# TPS61377_16V.net
KiCad netlist of a schematic drawn in Altium Designer
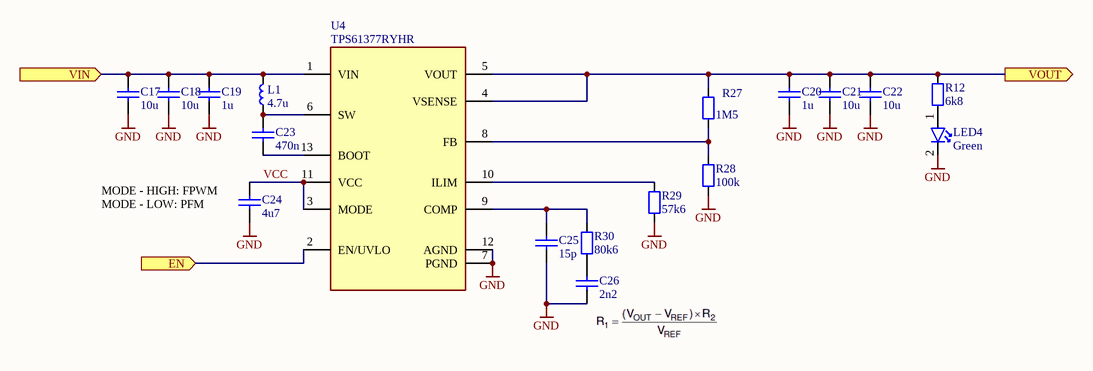
[diagram p0: TPS61377_16V.SchDoc]

(export (version "E")
  (design (tool "Eeschema 10.0.6"))
  (components
    (comp (ref "C17")
      (value "10u")
      (footprint "C_1206_3216Metric_IPC_N")
      (description "Generic MLCC with 1206 Footprint")
      (libsource (lib "database_library") (part "Capacitor_unpol"))
    )
    (comp (ref "C18")
      (value "10u")
      (footprint "C_1206_3216Metric_IPC_N")
      (description "Generic MLCC with 1206 Footprint")
      (libsource (lib "database_library") (part "Capacitor_unpol"))
    )
    (comp (ref "C19")
      (value "1u")
      (footprint "C_0402_1005Metric_IPC_N")
      (description "Generic MLCC with 0402 Footprint")
      (libsource (lib "database_library") (part "Capacitor_unpol"))
    )
    (comp (ref "C20")
      (value "1u")
      (footprint "C_0402_1005Metric_IPC_N")
      (description "Generic MLCC with 0402 Footprint")
      (libsource (lib "database_library") (part "Capacitor_unpol"))
    )
    (comp (ref "C21")
      (value "10u")
      (footprint "C_1206_3216Metric_IPC_N")
      (description "Generic MLCC with 1206 Footprint")
      (libsource (lib "database_library") (part "Capacitor_unpol"))
    )
    (comp (ref "C22")
      (value "10u")
      (footprint "C_1206_3216Metric_IPC_N")
      (description "Generic MLCC with 1206 Footprint")
      (libsource (lib "database_library") (part "Capacitor_unpol"))
    )
    (comp (ref "C23")
      (value "470n")
      (footprint "C_0402_1005Metric_IPC_N")
      (description "Generic MLCC with 0402 Footprint")
      (libsource (lib "database_library") (part "Capacitor_unpol"))
    )
    (comp (ref "C24")
      (value "4u7")
      (footprint "C_0402_1005Metric_IPC_N")
      (description "Generic MLCC with 0402 Footprint")
      (libsource (lib "database_library") (part "Capacitor_unpol"))
    )
    (comp (ref "C25")
      (value "15p")
      (footprint "C_0402_1005Metric_IPC_N")
      (description "Generic MLCC with 0402 Footprint")
      (libsource (lib "database_library") (part "Capacitor_unpol"))
    )
    (comp (ref "C26")
      (value "2n2")
      (footprint "C_0402_1005Metric_IPC_N")
      (description "Generic MLCC with 0402 Footprint")
      (libsource (lib "database_library") (part "Capacitor_unpol"))
    )
    (comp (ref "L1")
      (value "4.7u")
      (footprint "L_1616_4040Metric_IPC_N")
      (description "Power Inductor, 4.7u, 5A, , 57m, 20%, 1616")
      (fields (field (name "TOLERANCE") "20%") (field (name "MANUFACTURER") "Coilcraft"))
      (libsource (lib "database_library") (part "Inductor"))
    )
    (comp (ref "LED4")
      (value "Green")
      (footprint "LED_0603_1806Metric_IPC_N")
      (description "MLCC, Low Current, Green, 2.2V, 20mA, 0603")
      (fields
        (field (name "MANUFACTURER") "Broadcom / Avago")
        (field (name "MANUFACTURER PART NUMBER") "HSMG-C190")
      )
      (libsource (lib "database_library") (part "LED"))
    )
    (comp (ref "R12")
      (value "6k8")
      (footprint "R_0402_1005Metric_IPC_N")
      (description "Generic Chip Resistor with 0402 Footprint")
      (libsource (lib "database_library") (part "Resistor"))
    )
    (comp (ref "R27")
      (value "1M5")
      (footprint "R_0402_1005Metric_IPC_N")
      (description "Generic Chip Resistor with 0402 Footprint")
      (libsource (lib "database_library") (part "Resistor"))
    )
    (comp (ref "R28")
      (value "100k")
      (footprint "R_0402_1005Metric_IPC_N")
      (description "Generic Chip Resistor with 0402 Footprint")
      (libsource (lib "database_library") (part "Resistor"))
    )
    (comp (ref "R29")
      (value "57k6")
      (footprint "R_0402_1005Metric_IPC_N")
      (description "Generic Chip Resistor with 0402 Footprint")
      (libsource (lib "database_library") (part "Resistor"))
    )
    (comp (ref "R30")
      (value "80k6")
      (footprint "R_0402_1005Metric_IPC_N")
      (description "Generic Chip Resistor with 0402 Footprint")
      (libsource (lib "database_library") (part "Resistor"))
    )
    (comp (ref "U4")
      (value "TPS61377RYHR")
      (footprint "VQFN13_2_5x2")
      (fields (field (name "MANUFACTURER") "Texas Instruments"))
      (libsource (lib "database_library") (part "TPS61377RYHR"))
    )
  )
  (nets
    (net (code "1") (name "/EN") (class "Default")
      (node (ref "U4") (pin "2") (pinfunction "EN/UVLO_2") (pintype "passive"))
    )
    (net (code "2") (name "/VCC") (class "Default")
      (node (ref "C24") (pin "2") (pinfunction "2_2") (pintype "passive"))
      (node (ref "U4") (pin "11") (pinfunction "VCC_11") (pintype "passive"))
      (node (ref "U4") (pin "3") (pinfunction "MODE_3") (pintype "passive"))
    )
    (net (code "3") (name "/VIN") (class "Default")
      (node (ref "C17") (pin "2") (pinfunction "2_2") (pintype "passive"))
      (node (ref "C18") (pin "2") (pinfunction "2_2") (pintype "passive"))
      (node (ref "C19") (pin "2") (pinfunction "2_2") (pintype "passive"))
      (node (ref "L1") (pin "2") (pinfunction "2_2") (pintype "passive"))
      (node (ref "U4") (pin "1") (pinfunction "VIN_1") (pintype "passive"))
    )
    (net (code "4") (name "/VOUT") (class "Default")
      (node (ref "C20") (pin "2") (pinfunction "2_2") (pintype "passive"))
      (node (ref "C21") (pin "2") (pinfunction "2_2") (pintype "passive"))
      (node (ref "C22") (pin "2") (pinfunction "2_2") (pintype "passive"))
      (node (ref "R12") (pin "1") (pinfunction "1_1") (pintype "passive"))
      (node (ref "R27") (pin "2") (pinfunction "2_2") (pintype "passive"))
      (node (ref "U4") (pin "4") (pinfunction "VSENSE_4") (pintype "passive"))
      (node (ref "U4") (pin "5") (pinfunction "VOUT_5") (pintype "passive"))
    )
    (net (code "5") (name "GND") (class "Default")
      (node (ref "C17") (pin "1") (pinfunction "1_1") (pintype "passive"))
      (node (ref "C18") (pin "1") (pinfunction "1_1") (pintype "passive"))
      (node (ref "C19") (pin "1") (pinfunction "1_1") (pintype "passive"))
      (node (ref "C20") (pin "1") (pinfunction "1_1") (pintype "passive"))
      (node (ref "C21") (pin "1") (pinfunction "1_1") (pintype "passive"))
      (node (ref "C22") (pin "1") (pinfunction "1_1") (pintype "passive"))
      (node (ref "C24") (pin "1") (pinfunction "1_1") (pintype "passive"))
      (node (ref "C25") (pin "1") (pinfunction "1_1") (pintype "passive"))
      (node (ref "C26") (pin "1") (pinfunction "1_1") (pintype "passive"))
      (node (ref "LED4") (pin "2") (pinfunction "2_2") (pintype "passive"))
      (node (ref "R28") (pin "1") (pinfunction "1_1") (pintype "passive"))
      (node (ref "R29") (pin "1") (pinfunction "1_1") (pintype "passive"))
      (node (ref "U4") (pin "12") (pinfunction "AGND_12") (pintype "passive"))
      (node (ref "U4") (pin "7") (pinfunction "PGND_7") (pintype "passive"))
    )
    (net (code "6") (name "Net-(C26-Pad2)") (class "Default")
      (node (ref "C26") (pin "2") (pinfunction "2_2") (pintype "passive"))
      (node (ref "R30") (pin "1") (pinfunction "1_1") (pintype "passive"))
    )
    (net (code "7") (name "Net-(LED4-Pad1)") (class "Default")
      (node (ref "LED4") (pin "1") (pinfunction "1_1") (pintype "passive"))
      (node (ref "R12") (pin "2") (pinfunction "2_2") (pintype "passive"))
    )
    (net (code "8") (name "Net-(U4-BOOT)") (class "Default")
      (node (ref "C23") (pin "1") (pinfunction "1_1") (pintype "passive"))
      (node (ref "U4") (pin "13") (pinfunction "BOOT_13") (pintype "passive"))
    )
    (net (code "9") (name "Net-(U4-COMP)") (class "Default")
      (node (ref "C25") (pin "2") (pinfunction "2_2") (pintype "passive"))
      (node (ref "R30") (pin "2") (pinfunction "2_2") (pintype "passive"))
      (node (ref "U4") (pin "9") (pinfunction "COMP_9") (pintype "passive"))
    )
    (net (code "10") (name "Net-(U4-FB)") (class "Default")
      (node (ref "R27") (pin "1") (pinfunction "1_1") (pintype "passive"))
      (node (ref "R28") (pin "2") (pinfunction "2_2") (pintype "passive"))
      (node (ref "U4") (pin "8") (pinfunction "FB_8") (pintype "passive"))
    )
    (net (code "11") (name "Net-(U4-ILIM)") (class "Default")
      (node (ref "R29") (pin "2") (pinfunction "2_2") (pintype "passive"))
      (node (ref "U4") (pin "10") (pinfunction "ILIM_10") (pintype "passive"))
    )
    (net (code "12") (name "Net-(U4-SW)") (class "Default")
      (node (ref "C23") (pin "2") (pinfunction "2_2") (pintype "passive"))
      (node (ref "L1") (pin "1") (pinfunction "1_1") (pintype "passive"))
      (node (ref "U4") (pin "6") (pinfunction "SW_6") (pintype "passive"))
    )
  )
)
